# asynch9.net
KiCad netlist of a schematic drawn in EasyEDA
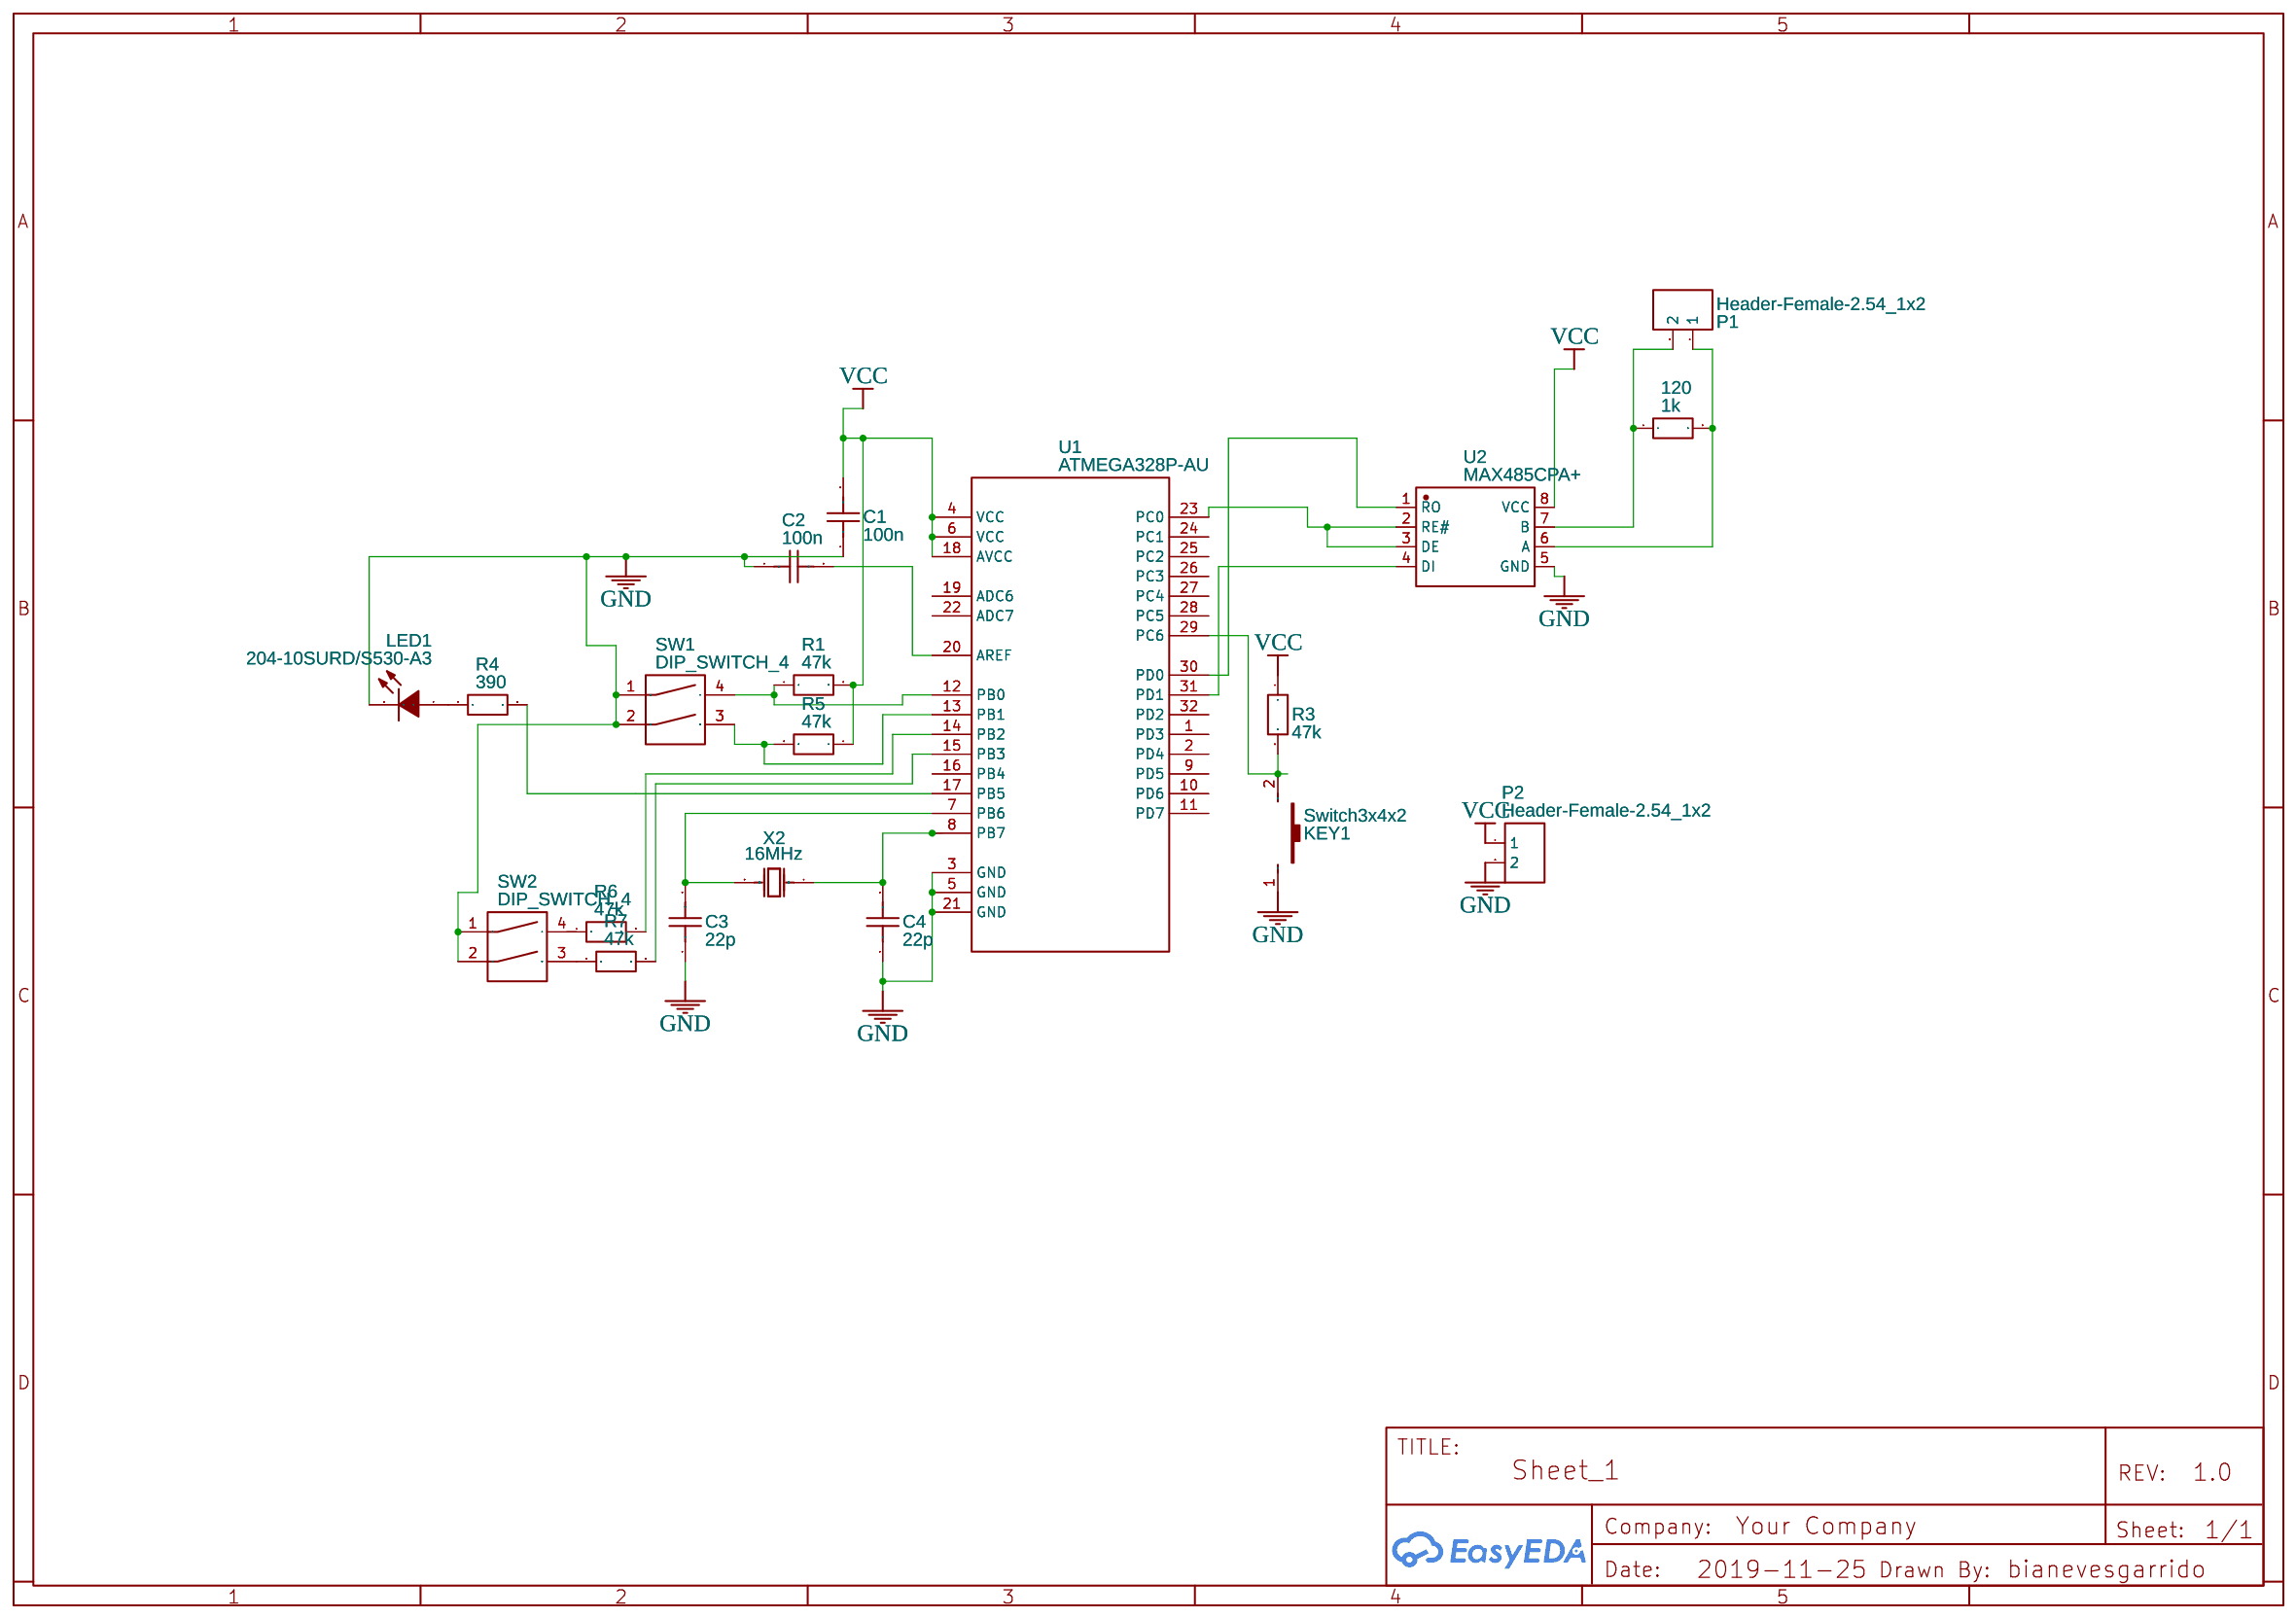
[diagram p0: schematic sheet]

(export (version "E")
  (design (tool "Eeschema 10.0.6"))
  (components
    (comp (ref "120") (value "1k") (libsource (lib "") (part "Res_AXIAL-0.3(1/8W)_EU_2")))
    (comp (ref "C1") (value "100n") (libsource (lib "") (part "Cap_RAD-0.1_US")))
    (comp (ref "C2") (value "100n") (libsource (lib "") (part "Cap_RAD-0.1_US_1")))
    (comp (ref "C3") (value "22p") (libsource (lib "") (part "Cap_RAD-0.1_US")))
    (comp (ref "C4") (value "22p") (libsource (lib "") (part "Cap_RAD-0.1_US")))
    (comp (ref "KEY1")
      (value "Switch3x4x2")
      (fields (field (name "BOM_Supplier Part") "C26638"))
      (libsource (lib "") (part "Unknown_645_415"))
    )
    (comp (ref "LED1")
      (value "204-10SURD/S530-A3")
      (fields (field (name "BOM_Supplier Part") "C99772"))
      (libsource (lib "") (part "Unknown_200_345"))
    )
    (comp (ref "P1")
      (value "Header-Female-2.54_1x2")
      (fields
        (field (name "BOM_Manufacturer Part") "2.54-1*2PFemale")
        (field (name "BOM_Supplier Part") "C49661")
      )
      (libsource (lib "") (part "Unknown_845_155"))
    )
    (comp (ref "P2")
      (value "Header-Female-2.54_1x2")
      (fields
        (field (name "BOM_Manufacturer Part") "2.54-1*2PFemale")
        (field (name "BOM_Supplier Part") "C49661")
      )
      (libsource (lib "") (part "Unknown_760_425"))
    )
    (comp (ref "R1") (value "47k") (libsource (lib "") (part "Res_AXIAL-0.3(1/8W)_EU")))
    (comp (ref "R3") (value "47k") (libsource (lib "") (part "Res_AXIAL-0.3(1/8W)_EU_1")))
    (comp (ref "R4") (value "390") (libsource (lib "") (part "Res_AXIAL-0.3(1/8W)_EU")))
    (comp (ref "R5") (value "47k") (libsource (lib "") (part "Res_AXIAL-0.3(1/8W)_EU_3")))
    (comp (ref "R6") (value "47k") (libsource (lib "") (part "Res_AXIAL-0.3(1/8W)_EU")))
    (comp (ref "R7") (value "47k") (libsource (lib "") (part "Res_AXIAL-0.3(1/8W)_EU")))
    (comp (ref "SW1") (value "DIP_SWITCH_4") (libsource (lib "") (part "Unknown_335_350")))
    (comp (ref "SW2") (value "DIP_SWITCH_4") (libsource (lib "") (part "Unknown_255_470")))
    (comp (ref "U1")
      (value "ATMEGA328P-AU")
      (fields (field (name "BOM_Supplier Part") "C14877"))
      (libsource (lib "") (part "Unknown_535_355"))
    )
    (comp (ref "U2")
      (value "MAX485CPA+")
      (fields (field (name "BOM_Supplier Part") "C77792"))
      (libsource (lib "") (part "Unknown_740_265"))
    )
    (comp (ref "X2")
      (value "16MHz")
      (fields
        (field (name "BOM_Manufacturer Part") "X49SD12MSD2SC")
        (field (name "BOM_Supplier Part") "C16369")
      )
      (libsource (lib "") (part "X49SD12MSD2SC"))
    )
  )
  (nets
    (net (code "1") (name "GND") (class "Default")
      (node (ref "C1") (pin "1") (pinfunction "1_1") (pintype "unspecified"))
      (node (ref "C2") (pin "1") (pinfunction "1_1") (pintype "unspecified"))
      (node (ref "C3") (pin "1") (pinfunction "1_1") (pintype "unspecified"))
      (node (ref "C4") (pin "1") (pinfunction "1_1") (pintype "unspecified"))
      (node (ref "KEY1") (pin "1") (pinfunction "1_1") (pintype "input"))
      (node (ref "LED1") (pin "2") (pinfunction "K_2") (pintype "unspecified"))
      (node (ref "P2") (pin "2") (pinfunction "2_2") (pintype "input"))
      (node (ref "SW1") (pin "1") (pinfunction "1_1") (pintype "unspecified"))
      (node (ref "SW1") (pin "2") (pinfunction "2_2") (pintype "unspecified"))
      (node (ref "SW2") (pin "1") (pinfunction "1_1") (pintype "unspecified"))
      (node (ref "SW2") (pin "2") (pinfunction "2_2") (pintype "unspecified"))
      (node (ref "U1") (pin "21") (pinfunction "GND_21") (pintype "unspecified"))
      (node (ref "U1") (pin "3") (pinfunction "GND_3") (pintype "unspecified"))
      (node (ref "U1") (pin "5") (pinfunction "GND_5") (pintype "unspecified"))
      (node (ref "U2") (pin "5") (pinfunction "GND_5") (pintype "unspecified"))
    )
    (net (code "2") (name "Net-(LED1-A)") (class "Default")
      (node (ref "LED1") (pin "1") (pinfunction "A_1") (pintype "unspecified"))
      (node (ref "R4") (pin "1") (pinfunction "1_1") (pintype "unspecified"))
    )
    (net (code "3") (name "Net-(R7-Pad1)") (class "Default")
      (node (ref "R7") (pin "1") (pinfunction "1_1") (pintype "unspecified"))
      (node (ref "SW2") (pin "3") (pinfunction "3_3") (pintype "unspecified"))
    )
    (net (code "4") (name "Net-(U1-AREF)") (class "Default")
      (node (ref "C2") (pin "2") (pinfunction "2_2") (pintype "unspecified"))
      (node (ref "U1") (pin "20") (pinfunction "AREF_20") (pintype "input"))
    )
    (net (code "5") (name "Net-(U1-PB0)") (class "Default")
      (node (ref "R1") (pin "1") (pinfunction "1_1") (pintype "unspecified"))
      (node (ref "SW1") (pin "4") (pinfunction "4_4") (pintype "unspecified"))
      (node (ref "U1") (pin "12") (pinfunction "PB0_12") (pintype "unspecified"))
    )
    (net (code "6") (name "Net-(U1-PB1)") (class "Default")
      (node (ref "R5") (pin "2") (pinfunction "2_2") (pintype "unspecified"))
      (node (ref "SW1") (pin "3") (pinfunction "3_3") (pintype "unspecified"))
      (node (ref "U1") (pin "13") (pinfunction "PB1_13") (pintype "unspecified"))
    )
    (net (code "7") (name "Net-(U1-PB2)") (class "Default")
      (node (ref "R6") (pin "2") (pinfunction "2_2") (pintype "unspecified"))
      (node (ref "U1") (pin "14") (pinfunction "PB2_14") (pintype "unspecified"))
    )
    (net (code "8") (name "Net-(U1-PB3)") (class "Default")
      (node (ref "R7") (pin "2") (pinfunction "2_2") (pintype "unspecified"))
      (node (ref "U1") (pin "15") (pinfunction "PB3_15") (pintype "unspecified"))
    )
    (net (code "9") (name "Net-(U1-PB5)") (class "Default")
      (node (ref "R4") (pin "2") (pinfunction "2_2") (pintype "unspecified"))
      (node (ref "U1") (pin "17") (pinfunction "PB5_17") (pintype "unspecified"))
    )
    (net (code "10") (name "Net-(U1-PB6)") (class "Default")
      (node (ref "C3") (pin "2") (pinfunction "2_2") (pintype "unspecified"))
      (node (ref "U1") (pin "7") (pinfunction "PB6_7") (pintype "unspecified"))
      (node (ref "X2") (pin "2") (pinfunction "OSC2_2") (pintype "input"))
    )
    (net (code "11") (name "Net-(U1-PB7)") (class "Default")
      (node (ref "C4") (pin "2") (pinfunction "2_2") (pintype "unspecified"))
      (node (ref "U1") (pin "8") (pinfunction "PB7_8") (pintype "unspecified"))
      (node (ref "X2") (pin "1") (pinfunction "OSC1_1") (pintype "input"))
    )
    (net (code "12") (name "Net-(U1-PC0)") (class "Default")
      (node (ref "U1") (pin "23") (pinfunction "PC0_23") (pintype "unspecified"))
      (node (ref "U2") (pin "2") (pinfunction "RE#_2") (pintype "unspecified"))
      (node (ref "U2") (pin "3") (pinfunction "DE_3") (pintype "unspecified"))
    )
    (net (code "13") (name "Net-(U1-PC6)") (class "Default")
      (node (ref "KEY1") (pin "2") (pinfunction "2_2") (pintype "input"))
      (node (ref "R3") (pin "2") (pinfunction "2_2") (pintype "unspecified"))
      (node (ref "U1") (pin "29") (pinfunction "PC6_29") (pintype "unspecified"))
    )
    (net (code "14") (name "Net-(U1-PD0)") (class "Default")
      (node (ref "U1") (pin "30") (pinfunction "PD0_30") (pintype "unspecified"))
      (node (ref "U2") (pin "1") (pinfunction "RO_1") (pintype "unspecified"))
    )
    (net (code "15") (name "Net-(U1-PD1)") (class "Default")
      (node (ref "U1") (pin "31") (pinfunction "PD1_31") (pintype "unspecified"))
      (node (ref "U2") (pin "4") (pinfunction "DI_4") (pintype "unspecified"))
    )
    (net (code "16") (name "Net-(U2-A)") (class "Default")
      (node (ref "120") (pin "2") (pinfunction "2_2") (pintype "unspecified"))
      (node (ref "P1") (pin "1") (pinfunction "1_1") (pintype "input"))
      (node (ref "U2") (pin "6") (pinfunction "A_6") (pintype "unspecified"))
    )
    (net (code "17") (name "Net-(U2-B)") (class "Default")
      (node (ref "120") (pin "1") (pinfunction "1_1") (pintype "unspecified"))
      (node (ref "P1") (pin "2") (pinfunction "2_2") (pintype "input"))
      (node (ref "U2") (pin "7") (pinfunction "B_7") (pintype "unspecified"))
    )
    (net (code "18") (name "VCC") (class "Default")
      (node (ref "C1") (pin "2") (pinfunction "2_2") (pintype "unspecified"))
      (node (ref "P2") (pin "1") (pinfunction "1_1") (pintype "input"))
      (node (ref "R1") (pin "2") (pinfunction "2_2") (pintype "unspecified"))
      (node (ref "R3") (pin "1") (pinfunction "1_1") (pintype "unspecified"))
      (node (ref "R5") (pin "1") (pinfunction "1_1") (pintype "unspecified"))
      (node (ref "U1") (pin "18") (pinfunction "AVCC_18") (pintype "passive"))
      (node (ref "U1") (pin "4") (pinfunction "VCC_4") (pintype "passive"))
      (node (ref "U1") (pin "6") (pinfunction "VCC_6") (pintype "passive"))
      (node (ref "U2") (pin "8") (pinfunction "VCC_8") (pintype "unspecified"))
    )
    (net (code "19") (name "unconnected-(R6-Pad1)") (class "Default")
      (node (ref "R6") (pin "1") (pinfunction "1_1") (pintype "unspecified"))
    )
    (net (code "20") (name "unconnected-(SW2-Pad4)") (class "Default")
      (node (ref "SW2") (pin "4") (pinfunction "4_4") (pintype "unspecified"))
    )
    (net (code "21") (name "unconnected-(U1-ADC6-Pad19)") (class "Default")
      (node (ref "U1") (pin "19") (pinfunction "ADC6_19") (pintype "input"))
    )
    (net (code "22") (name "unconnected-(U1-ADC7-Pad22)") (class "Default")
      (node (ref "U1") (pin "22") (pinfunction "ADC7_22") (pintype "input"))
    )
    (net (code "23") (name "unconnected-(U1-PB4-Pad16)") (class "Default")
      (node (ref "U1") (pin "16") (pinfunction "PB4_16") (pintype "unspecified"))
    )
    (net (code "24") (name "unconnected-(U1-PC1-Pad24)") (class "Default")
      (node (ref "U1") (pin "24") (pinfunction "PC1_24") (pintype "unspecified"))
    )
    (net (code "25") (name "unconnected-(U1-PC2-Pad25)") (class "Default")
      (node (ref "U1") (pin "25") (pinfunction "PC2_25") (pintype "unspecified"))
    )
    (net (code "26") (name "unconnected-(U1-PC3-Pad26)") (class "Default")
      (node (ref "U1") (pin "26") (pinfunction "PC3_26") (pintype "unspecified"))
    )
    (net (code "27") (name "unconnected-(U1-PC4-Pad27)") (class "Default")
      (node (ref "U1") (pin "27") (pinfunction "PC4_27") (pintype "unspecified"))
    )
    (net (code "28") (name "unconnected-(U1-PC5-Pad28)") (class "Default")
      (node (ref "U1") (pin "28") (pinfunction "PC5_28") (pintype "unspecified"))
    )
    (net (code "29") (name "unconnected-(U1-PD2-Pad32)") (class "Default")
      (node (ref "U1") (pin "32") (pinfunction "PD2_32") (pintype "unspecified"))
    )
    (net (code "30") (name "unconnected-(U1-PD3-Pad1)") (class "Default")
      (node (ref "U1") (pin "1") (pinfunction "PD3_1") (pintype "unspecified"))
    )
    (net (code "31") (name "unconnected-(U1-PD4-Pad2)") (class "Default")
      (node (ref "U1") (pin "2") (pinfunction "PD4_2") (pintype "unspecified"))
    )
    (net (code "32") (name "unconnected-(U1-PD5-Pad9)") (class "Default")
      (node (ref "U1") (pin "9") (pinfunction "PD5_9") (pintype "unspecified"))
    )
    (net (code "33") (name "unconnected-(U1-PD6-Pad10)") (class "Default")
      (node (ref "U1") (pin "10") (pinfunction "PD6_10") (pintype "unspecified"))
    )
    (net (code "34") (name "unconnected-(U1-PD7-Pad11)") (class "Default")
      (node (ref "U1") (pin "11") (pinfunction "PD7_11") (pintype "unspecified"))
    )
  )
)
